# tetris.net
KiCad netlist of a schematic drawn in EAGLE
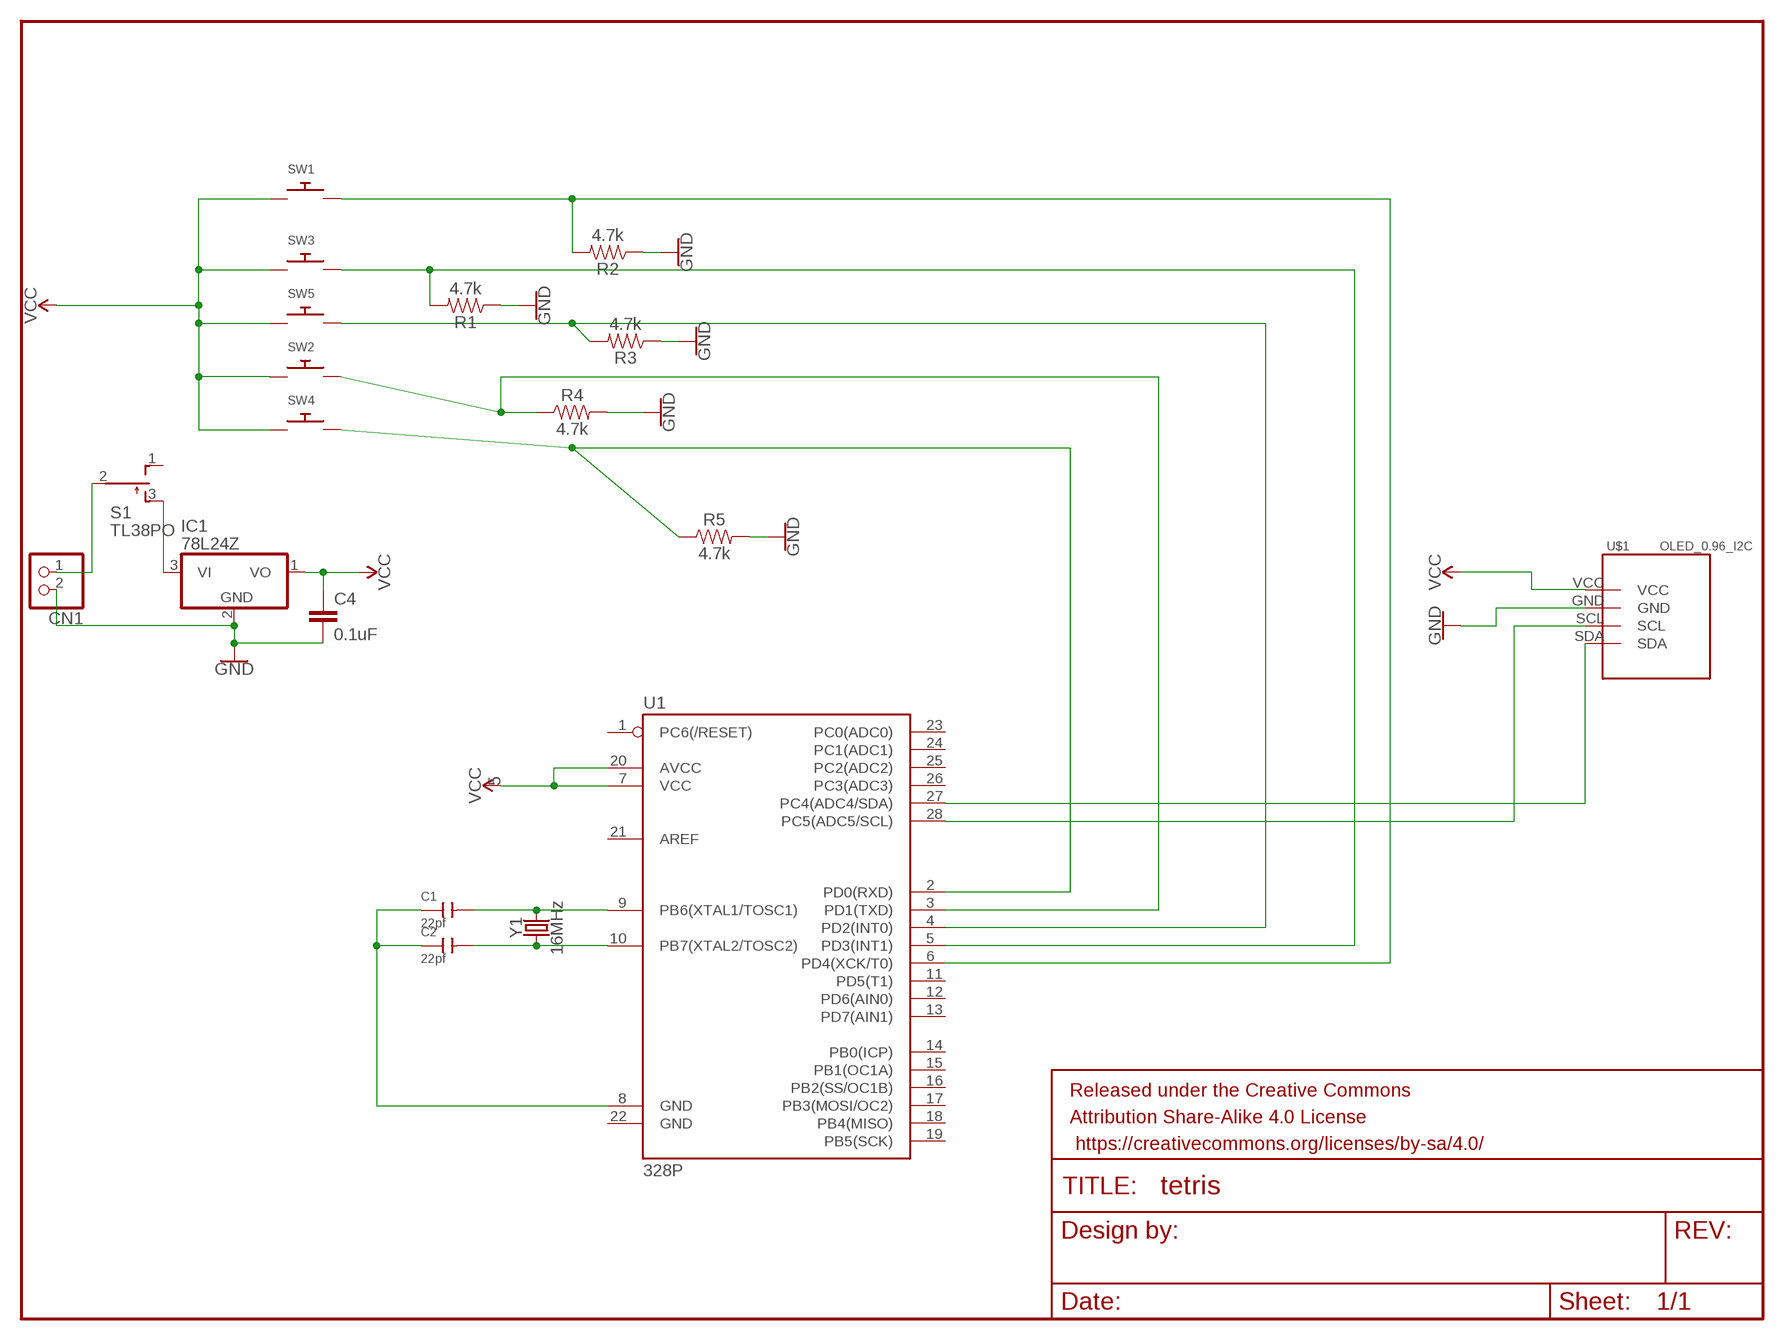
[diagram p0: schematic, sheet 1]

(export (version "E")
  (design (tool "Eeschema 10.0.6"))
  (components
    (comp (ref "C1")
      (value "22pf")
      (footprint "eagle-import:C0402")
      (fields (field (name "MPN") "CC0402JRNPO9BN220"))
      (libsource (lib "eagle-import") (part "CERAMIC-22PF-50V-5%-NPO(0402)"))
    )
    (comp (ref "C2")
      (value "22pf")
      (footprint "eagle-import:C0402")
      (fields (field (name "MPN") "CC0402JRNPO9BN220"))
      (libsource (lib "eagle-import") (part "CERAMIC-22PF-50V-5%-NPO(0402)"))
    )
    (comp (ref "C4")
      (value "0.1uF")
      (footprint "eagle-import:0402")
      (libsource (lib "eagle-import") (part "0.1UF-0402-16V-10%"))
    )
    (comp (ref "CN1")
      (value "JST_2PIN-SMT-RA")
      (footprint "eagle-import:JST-PH-2-SMT-RA")
      (libsource (lib "eagle-import") (part "JST_2PIN-SMT-RA"))
    )
    (comp (ref "FRAME1")
      (value "FRAME-LETTERNO_PACKAGE")
      (footprint "eagle-import:DUMMY")
      (fields (field (name "DESIGNER") "Nobody"))
      (libsource (lib "eagle-import") (part "FRAME-LETTERNO_PACKAGE"))
    )
    (comp (ref "IC1")
      (value "78L24Z")
      (footprint "eagle-import:TO92")
      (libsource (lib "eagle-import") (part "78ZL24"))
    )
    (comp (ref "R1")
      (value "4.7k")
      (footprint "eagle-import:0603")
      (libsource (lib "eagle-import") (part "4.7KOHM-0603-1/10W-1%"))
    )
    (comp (ref "R2")
      (value "4.7k")
      (footprint "eagle-import:0603")
      (libsource (lib "eagle-import") (part "4.7KOHM-0603-1/10W-1%"))
    )
    (comp (ref "R3")
      (value "4.7k")
      (footprint "eagle-import:0603")
      (libsource (lib "eagle-import") (part "4.7KOHM-0603-1/10W-1%"))
    )
    (comp (ref "R4")
      (value "4.7k")
      (footprint "eagle-import:0603")
      (libsource (lib "eagle-import") (part "4.7KOHM-0603-1/10W-1%"))
    )
    (comp (ref "R5")
      (value "4.7k")
      (footprint "eagle-import:0603")
      (libsource (lib "eagle-import") (part "4.7KOHM-0603-1/10W-1%"))
    )
    (comp (ref "S1")
      (value "TL38PO")
      (footprint "eagle-import:TL3XPO")
      (libsource (lib "eagle-import") (part "TL38PO"))
    )
    (comp (ref "SW1")
      (value "SWITCH_PUSHBUTTONC&K_KSS")
      (footprint "eagle-import:BTN_CK_KSS")
      (libsource (lib "eagle-import") (part "SWITCH_PUSHBUTTONC&K_KSS"))
    )
    (comp (ref "SW2")
      (value "SWITCH_PUSHBUTTONC&K_KSS")
      (footprint "eagle-import:BTN_CK_KSS")
      (libsource (lib "eagle-import") (part "SWITCH_PUSHBUTTONC&K_KSS"))
    )
    (comp (ref "SW3")
      (value "SWITCH_PUSHBUTTONC&K_KSS")
      (footprint "eagle-import:BTN_CK_KSS")
      (libsource (lib "eagle-import") (part "SWITCH_PUSHBUTTONC&K_KSS"))
    )
    (comp (ref "SW4")
      (value "SWITCH_PUSHBUTTONC&K_KSS")
      (footprint "eagle-import:BTN_CK_KSS")
      (libsource (lib "eagle-import") (part "SWITCH_PUSHBUTTONC&K_KSS"))
    )
    (comp (ref "SW5")
      (value "SWITCH_PUSHBUTTONC&K_KSS")
      (footprint "eagle-import:BTN_CK_KSS")
      (libsource (lib "eagle-import") (part "SWITCH_PUSHBUTTONC&K_KSS"))
    )
    (comp (ref "U$1")
      (value "OLED_0.96_I2C")
      (footprint "eagle-import:OLED_0.96_I2C")
      (libsource (lib "eagle-import") (part "OLED_0.96_I2C"))
    )
    (comp (ref "U1")
      (value "328P")
      (footprint "eagle-import:DIP28")
      (libsource (lib "eagle-import") (part "ATMEGA328P_PDIP"))
    )
    (comp (ref "Y1")
      (value "16MHz")
      (footprint "eagle-import:HC49US")
      (libsource (lib "eagle-import") (part "CRYSTAL-16MHZPTH-HC49US"))
    )
  )
  (nets
    (net (code "1") (name "GND") (class "Default")
      (node (ref "C4") (pin "2") (pinfunction "2_2") (pintype "passive"))
      (node (ref "CN1") (pin "2") (pinfunction "1_2") (pintype "passive"))
      (node (ref "IC1") (pin "2") (pinfunction "GND_2") (pintype "passive"))
      (node (ref "R1") (pin "1") (pinfunction "1_1") (pintype "passive"))
      (node (ref "R2") (pin "1") (pinfunction "1_1") (pintype "passive"))
      (node (ref "R3") (pin "1") (pinfunction "1_1") (pintype "passive"))
      (node (ref "R4") (pin "2") (pinfunction "2_2") (pintype "passive"))
      (node (ref "R5") (pin "2") (pinfunction "2_2") (pintype "passive"))
      (node (ref "U$1") (pin "GND") (pinfunction "GND_GND") (pintype "bidirectional"))
    )
    (net (code "2") (name "Net-(C1-Pad1)") (class "Default")
      (node (ref "C1") (pin "1") (pinfunction "1_1") (pintype "passive"))
      (node (ref "C2") (pin "1") (pinfunction "1_1") (pintype "passive"))
      (node (ref "U1") (pin "8") (pinfunction "GND_8") (pintype "bidirectional"))
    )
    (net (code "3") (name "Net-(CN1-2)") (class "Default")
      (node (ref "CN1") (pin "1") (pinfunction "2_1") (pintype "passive"))
      (node (ref "S1") (pin "2") (pinfunction "P_2") (pintype "passive"))
    )
    (net (code "4") (name "Net-(IC1-VI)") (class "Default")
      (node (ref "IC1") (pin "3") (pinfunction "VI_3") (pintype "input"))
      (node (ref "S1") (pin "3") (pinfunction "S_3") (pintype "passive"))
    )
    (net (code "5") (name "Net-(U1-PB6(XTAL1{slash}TOSC1))") (class "Default")
      (node (ref "C1") (pin "2") (pinfunction "2_2") (pintype "passive"))
      (node (ref "U1") (pin "9") (pinfunction "PB6(XTAL1/TOSC1)_9") (pintype "bidirectional"))
      (node (ref "Y1") (pin "2") (pinfunction "2_2") (pintype "passive"))
    )
    (net (code "6") (name "Net-(U1-PB7(XTAL2{slash}TOSC2))") (class "Default")
      (node (ref "C2") (pin "2") (pinfunction "2_2") (pintype "passive"))
      (node (ref "U1") (pin "10") (pinfunction "PB7(XTAL2/TOSC2)_10") (pintype "bidirectional"))
      (node (ref "Y1") (pin "1") (pinfunction "1_1") (pintype "passive"))
    )
    (net (code "7") (name "Net-(U1-PC4(ADC4{slash}SDA))") (class "Default")
      (node (ref "U$1") (pin "SDA") (pinfunction "SDA_SDA") (pintype "bidirectional"))
      (node (ref "U1") (pin "27") (pinfunction "PC4(ADC4/SDA)_27") (pintype "bidirectional"))
    )
    (net (code "8") (name "Net-(U1-PC5(ADC5{slash}SCL))") (class "Default")
      (node (ref "U$1") (pin "SCL") (pinfunction "SCL_SCL") (pintype "bidirectional"))
      (node (ref "U1") (pin "28") (pinfunction "PC5(ADC5/SCL)_28") (pintype "bidirectional"))
    )
    (net (code "9") (name "Net-(U1-PD0(RXD))") (class "Default")
      (node (ref "R5") (pin "1") (pinfunction "1_1") (pintype "passive"))
      (node (ref "SW4") (pin "P$2") (pinfunction "P$2_P$2") (pintype "passive"))
      (node (ref "U1") (pin "2") (pinfunction "PD0(RXD)_2") (pintype "bidirectional"))
    )
    (net (code "10") (name "Net-(U1-PD1(TXD))") (class "Default")
      (node (ref "R4") (pin "1") (pinfunction "1_1") (pintype "passive"))
      (node (ref "SW2") (pin "P$2") (pinfunction "P$2_P$2") (pintype "passive"))
      (node (ref "U1") (pin "3") (pinfunction "PD1(TXD)_3") (pintype "bidirectional"))
    )
    (net (code "11") (name "Net-(U1-PD2(INT0))") (class "Default")
      (node (ref "R3") (pin "2") (pinfunction "2_2") (pintype "passive"))
      (node (ref "SW5") (pin "P$2") (pinfunction "P$2_P$2") (pintype "passive"))
      (node (ref "U1") (pin "4") (pinfunction "PD2(INT0)_4") (pintype "bidirectional"))
    )
    (net (code "12") (name "Net-(U1-PD3(INT1))") (class "Default")
      (node (ref "R1") (pin "2") (pinfunction "2_2") (pintype "passive"))
      (node (ref "SW3") (pin "P$2") (pinfunction "P$2_P$2") (pintype "passive"))
      (node (ref "U1") (pin "5") (pinfunction "PD3(INT1)_5") (pintype "bidirectional"))
    )
    (net (code "13") (name "Net-(U1-PD4(XCK{slash}T0))") (class "Default")
      (node (ref "R2") (pin "2") (pinfunction "2_2") (pintype "passive"))
      (node (ref "SW1") (pin "P$2") (pinfunction "P$2_P$2") (pintype "passive"))
      (node (ref "U1") (pin "6") (pinfunction "PD4(XCK/T0)_6") (pintype "bidirectional"))
    )
    (net (code "14") (name "VCC") (class "Default")
      (node (ref "C4") (pin "1") (pinfunction "1_1") (pintype "passive"))
      (node (ref "IC1") (pin "1") (pinfunction "VO_1") (pintype "passive"))
      (node (ref "SW1") (pin "P$1") (pinfunction "P$1_P$1") (pintype "passive"))
      (node (ref "SW2") (pin "P$1") (pinfunction "P$1_P$1") (pintype "passive"))
      (node (ref "SW3") (pin "P$1") (pinfunction "P$1_P$1") (pintype "passive"))
      (node (ref "SW4") (pin "P$1") (pinfunction "P$1_P$1") (pintype "passive"))
      (node (ref "SW5") (pin "P$1") (pinfunction "P$1_P$1") (pintype "passive"))
      (node (ref "U$1") (pin "VCC") (pinfunction "VCC_VCC") (pintype "bidirectional"))
      (node (ref "U1") (pin "20") (pinfunction "AVCC_20") (pintype "bidirectional"))
      (node (ref "U1") (pin "7") (pinfunction "VCC_7") (pintype "bidirectional"))
    )
    (net (code "15") (name "unconnected-(S1-O-Pad1)") (class "Default")
      (node (ref "S1") (pin "1") (pinfunction "O_1") (pintype "passive"))
    )
    (net (code "16") (name "unconnected-(U1-AREF-Pad21)") (class "Default")
      (node (ref "U1") (pin "21") (pinfunction "AREF_21") (pintype "bidirectional"))
    )
    (net (code "17") (name "unconnected-(U1-GND-Pad22)") (class "Default")
      (node (ref "U1") (pin "22") (pinfunction "GND_22") (pintype "bidirectional"))
    )
    (net (code "18") (name "unconnected-(U1-PB0(ICP)-Pad14)") (class "Default")
      (node (ref "U1") (pin "14") (pinfunction "PB0(ICP)_14") (pintype "bidirectional"))
    )
    (net (code "19") (name "unconnected-(U1-PB1(OC1A)-Pad15)") (class "Default")
      (node (ref "U1") (pin "15") (pinfunction "PB1(OC1A)_15") (pintype "bidirectional"))
    )
    (net (code "20") (name "unconnected-(U1-PB2(SS{slash}OC1B)-Pad16)") (class "Default")
      (node (ref "U1") (pin "16") (pinfunction "PB2(SS/OC1B)_16") (pintype "bidirectional"))
    )
    (net (code "21") (name "unconnected-(U1-PB3(MOSI{slash}OC2)-Pad17)") (class "Default")
      (node (ref "U1") (pin "17") (pinfunction "PB3(MOSI/OC2)_17") (pintype "bidirectional"))
    )
    (net (code "22") (name "unconnected-(U1-PB4(MISO)-Pad18)") (class "Default")
      (node (ref "U1") (pin "18") (pinfunction "PB4(MISO)_18") (pintype "bidirectional"))
    )
    (net (code "23") (name "unconnected-(U1-PB5(SCK)-Pad19)") (class "Default")
      (node (ref "U1") (pin "19") (pinfunction "PB5(SCK)_19") (pintype "bidirectional"))
    )
    (net (code "24") (name "unconnected-(U1-PC0(ADC0)-Pad23)") (class "Default")
      (node (ref "U1") (pin "23") (pinfunction "PC0(ADC0)_23") (pintype "bidirectional"))
    )
    (net (code "25") (name "unconnected-(U1-PC1(ADC1)-Pad24)") (class "Default")
      (node (ref "U1") (pin "24") (pinfunction "PC1(ADC1)_24") (pintype "bidirectional"))
    )
    (net (code "26") (name "unconnected-(U1-PC2(ADC2)-Pad25)") (class "Default")
      (node (ref "U1") (pin "25") (pinfunction "PC2(ADC2)_25") (pintype "bidirectional"))
    )
    (net (code "27") (name "unconnected-(U1-PC3(ADC3)-Pad26)") (class "Default")
      (node (ref "U1") (pin "26") (pinfunction "PC3(ADC3)_26") (pintype "bidirectional"))
    )
    (net (code "28") (name "unconnected-(U1-PC6({slash}RESET)-Pad1)") (class "Default")
      (node (ref "U1") (pin "1") (pinfunction "PC6(/RESET)_1") (pintype "bidirectional"))
    )
    (net (code "29") (name "unconnected-(U1-PD5(T1)-Pad11)") (class "Default")
      (node (ref "U1") (pin "11") (pinfunction "PD5(T1)_11") (pintype "bidirectional"))
    )
    (net (code "30") (name "unconnected-(U1-PD6(AIN0)-Pad12)") (class "Default")
      (node (ref "U1") (pin "12") (pinfunction "PD6(AIN0)_12") (pintype "bidirectional"))
    )
    (net (code "31") (name "unconnected-(U1-PD7(AIN1)-Pad13)") (class "Default")
      (node (ref "U1") (pin "13") (pinfunction "PD7(AIN1)_13") (pintype "bidirectional"))
    )
  )
)
